# Sch.net
KiCad netlist of a schematic drawn in EasyEDA
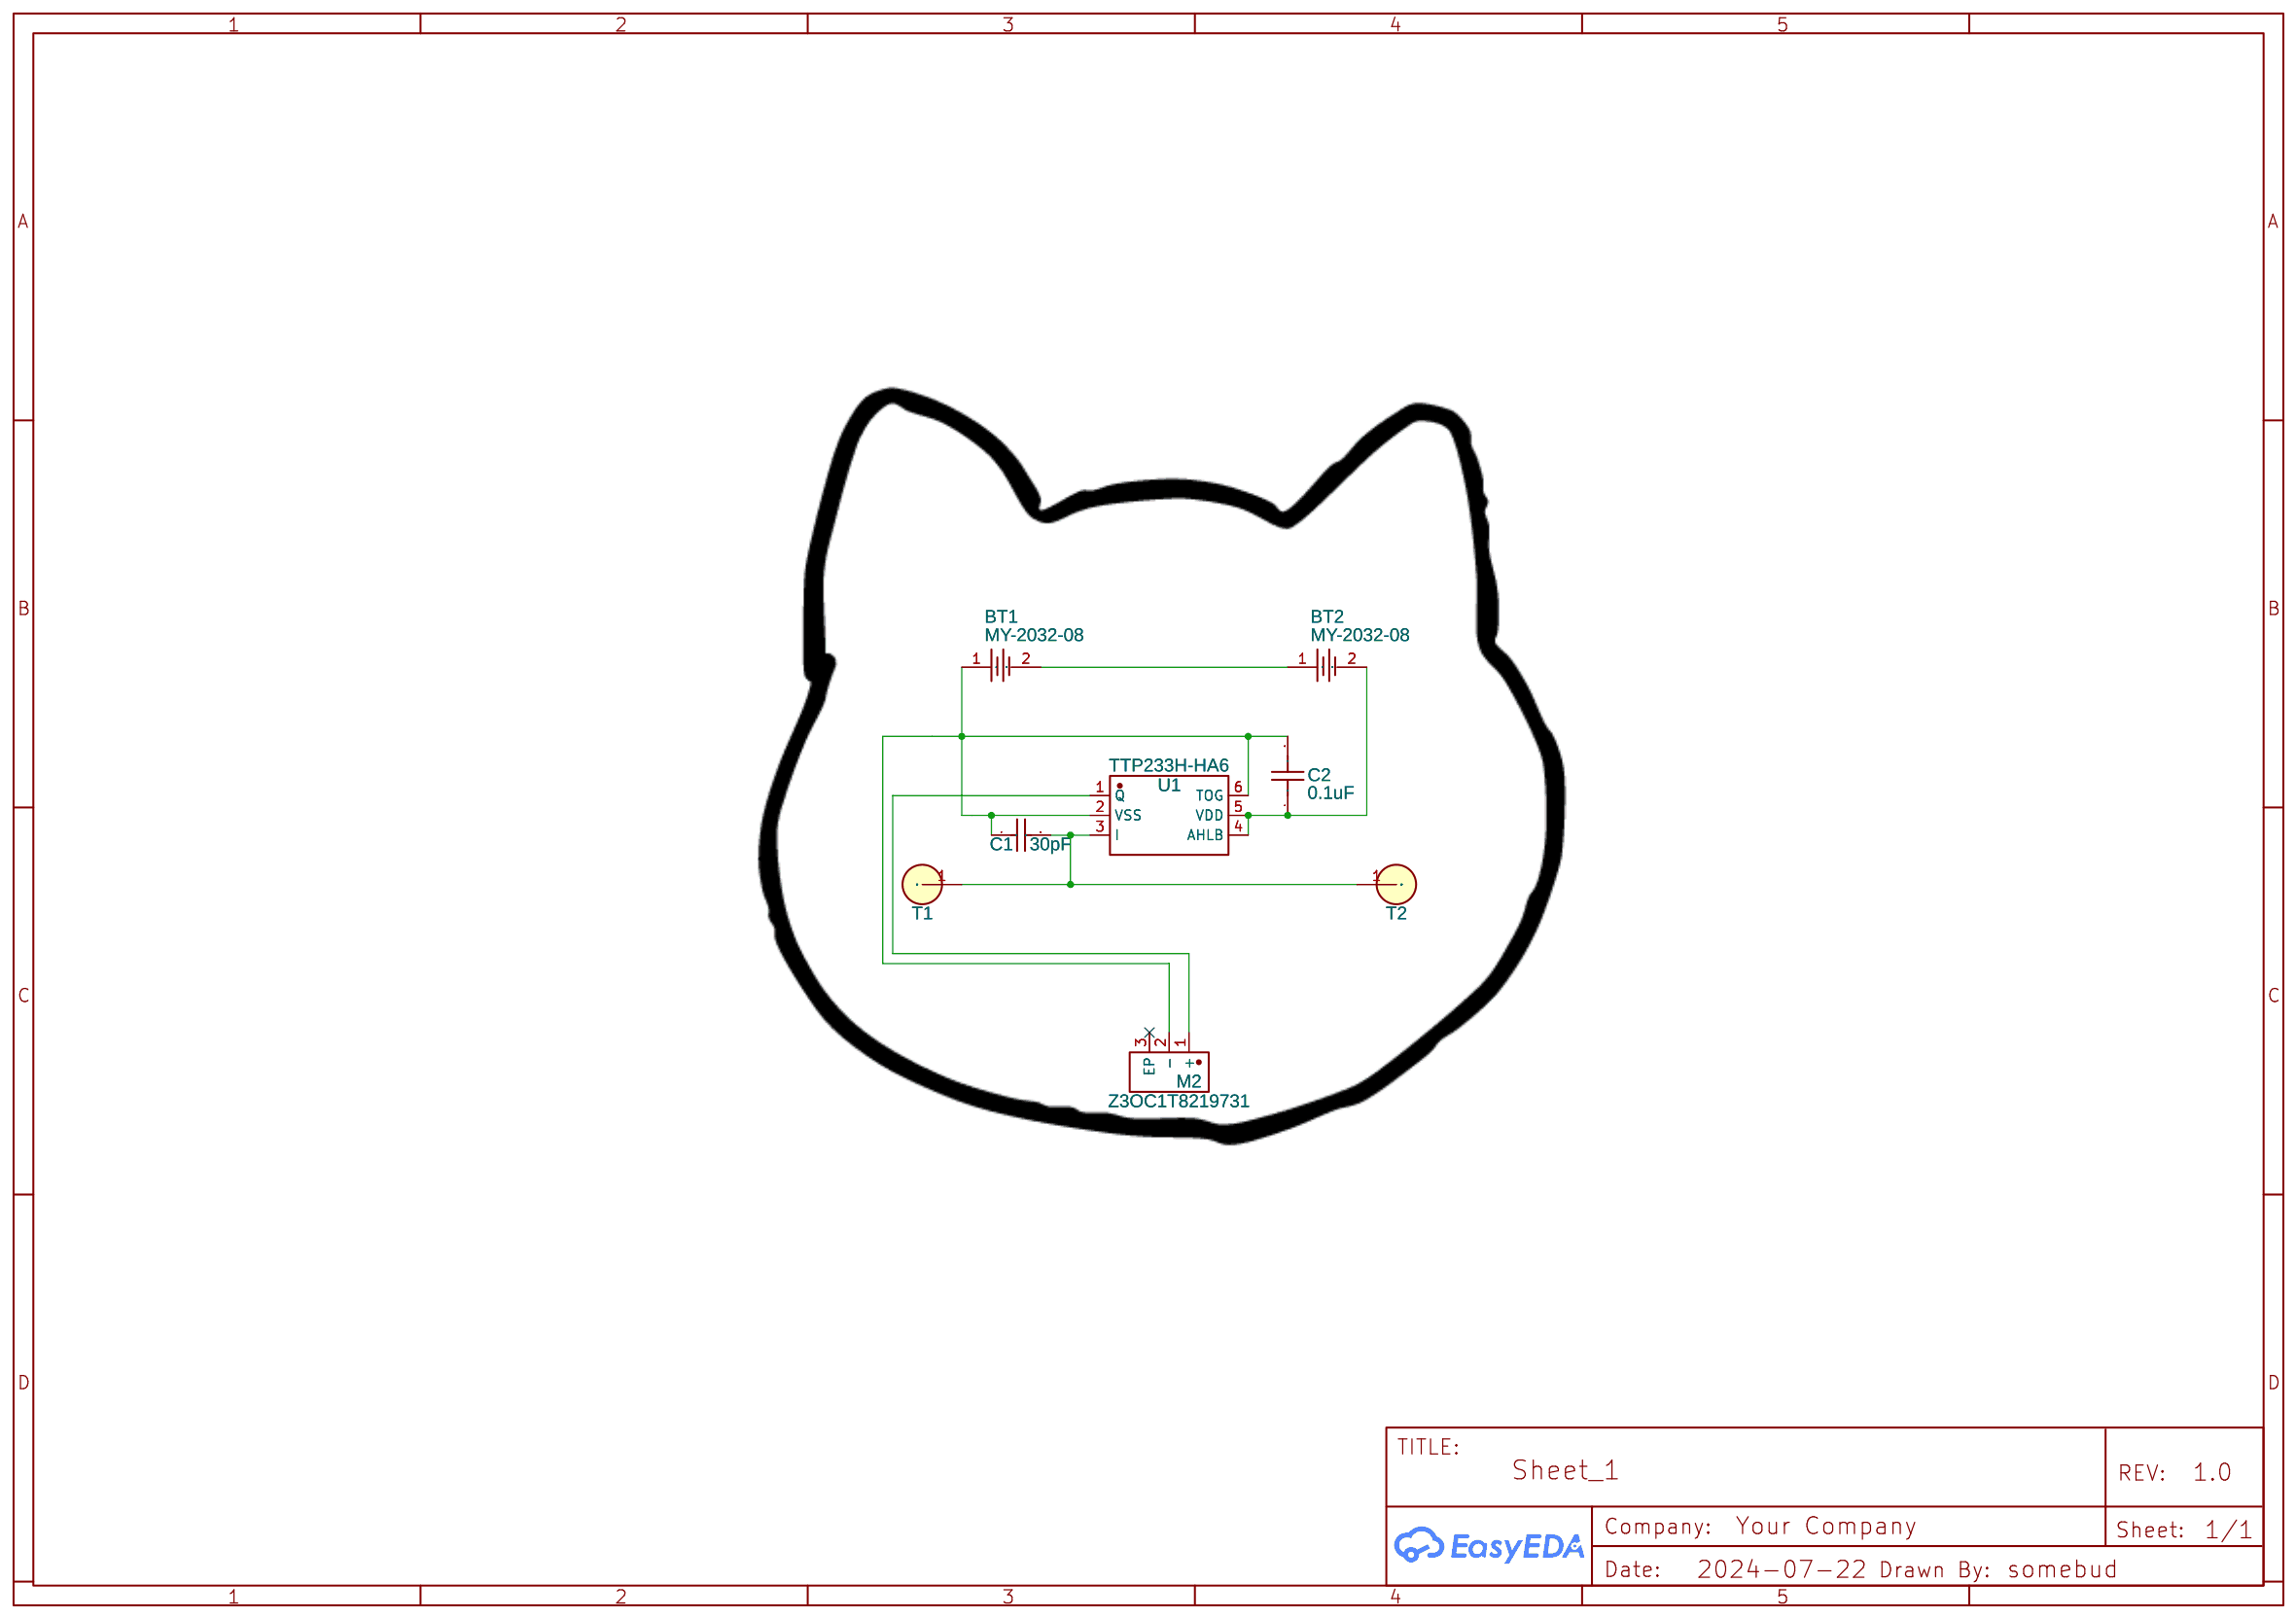
[diagram p0: schematic sheet]

(export (version "E")
  (design (tool "Eeschema 10.0.6"))
  (components
    (comp (ref "BT1")
      (value "MY-2032-08")
      (fields (field (name "Manufacturer") "MYOUNG(美阳)"))
      (libsource (lib "") (part "MY-2032-08"))
    )
    (comp (ref "BT2")
      (value "MY-2032-08")
      (fields (field (name "Manufacturer") "MYOUNG(美阳)"))
      (libsource (lib "") (part "MY-2032-08"))
    )
    (comp (ref "C1")
      (value "30pF")
      (fields (field (name "Manufacturer Part") "0603CG300J500NT") (field (name "Manufacturer") "FH(风华)"))
      (libsource (lib "") (part "0603CG300J500NT"))
    )
    (comp (ref "C2") (value "0.1uF") (libsource (lib "") (part "C_0603_US")))
    (comp (ref "M2")
      (value "Z3OC1T8219731")
      (fields (field (name "Manufacturer") "KOTL(金龙机电)"))
      (libsource (lib "") (part "Z3OC1T8219731"))
    )
    (comp (ref "T1")
      (value "TOUCHPAD 12mm circle nopaste nomask")
      (libsource (lib "") (part "TOUCHPAD 12mm circle nopaste nomask_1"))
    )
    (comp (ref "T2")
      (value "TOUCHPAD 12mm circle nopaste nomask")
      (libsource (lib "") (part "TOUCHPAD 12mm circle nopaste nomask"))
    )
    (comp (ref "U1")
      (value "TTP233H-HA6")
      (fields (field (name "Manufacturer") "TONTEK(通泰)"))
      (libsource (lib "") (part "TTP233H-HA6"))
    )
  )
  (nets
    (net (code "1") (name "Net-(BT1-Pad2)") (class "Default")
      (node (ref "BT1") (pin "2") (pinfunction "2_2") (pintype "input"))
      (node (ref "BT2") (pin "1") (pinfunction "1_1") (pintype "input"))
    )
    (net (code "2") (name "Net-(M2-+)") (class "Default")
      (node (ref "M2") (pin "1") (pinfunction "+_1") (pintype "unspecified"))
      (node (ref "U1") (pin "1") (pinfunction "Q_1") (pintype "unspecified"))
    )
    (net (code "3") (name "Net-(M2--)") (class "Default")
      (node (ref "BT1") (pin "1") (pinfunction "1_1") (pintype "input"))
      (node (ref "C1") (pin "1") (pinfunction "1_1") (pintype "input"))
      (node (ref "C2") (pin "2") (pinfunction "2_2") (pintype "unspecified"))
      (node (ref "M2") (pin "2") (pinfunction "-_2") (pintype "unspecified"))
      (node (ref "U1") (pin "2") (pinfunction "VSS_2") (pintype "unspecified"))
      (node (ref "U1") (pin "6") (pinfunction "TOG_6") (pintype "unspecified"))
    )
    (net (code "4") (name "Net-(T1-Touch)") (class "Default")
      (node (ref "C1") (pin "2") (pinfunction "2_2") (pintype "input"))
      (node (ref "T1") (pin "1") (pinfunction "Touch_1") (pintype "unspecified"))
      (node (ref "T2") (pin "1") (pinfunction "Touch_1") (pintype "unspecified"))
      (node (ref "U1") (pin "3") (pinfunction "I_3") (pintype "unspecified"))
    )
    (net (code "5") (name "Net-(U1-AHLB)") (class "Default")
      (node (ref "BT2") (pin "2") (pinfunction "2_2") (pintype "input"))
      (node (ref "C2") (pin "1") (pinfunction "1_1") (pintype "unspecified"))
      (node (ref "U1") (pin "4") (pinfunction "AHLB_4") (pintype "unspecified"))
      (node (ref "U1") (pin "5") (pinfunction "VDD_5") (pintype "unspecified"))
    )
    (net (code "6") (name "unconnected-(M2-EP-Pad3)") (class "Default")
      (node (ref "M2") (pin "3") (pinfunction "EP_3") (pintype "unspecified+no_connect"))
    )
  )
)
